# chernov_motherboard.net
KiCad netlist of a schematic drawn in Altium Designer
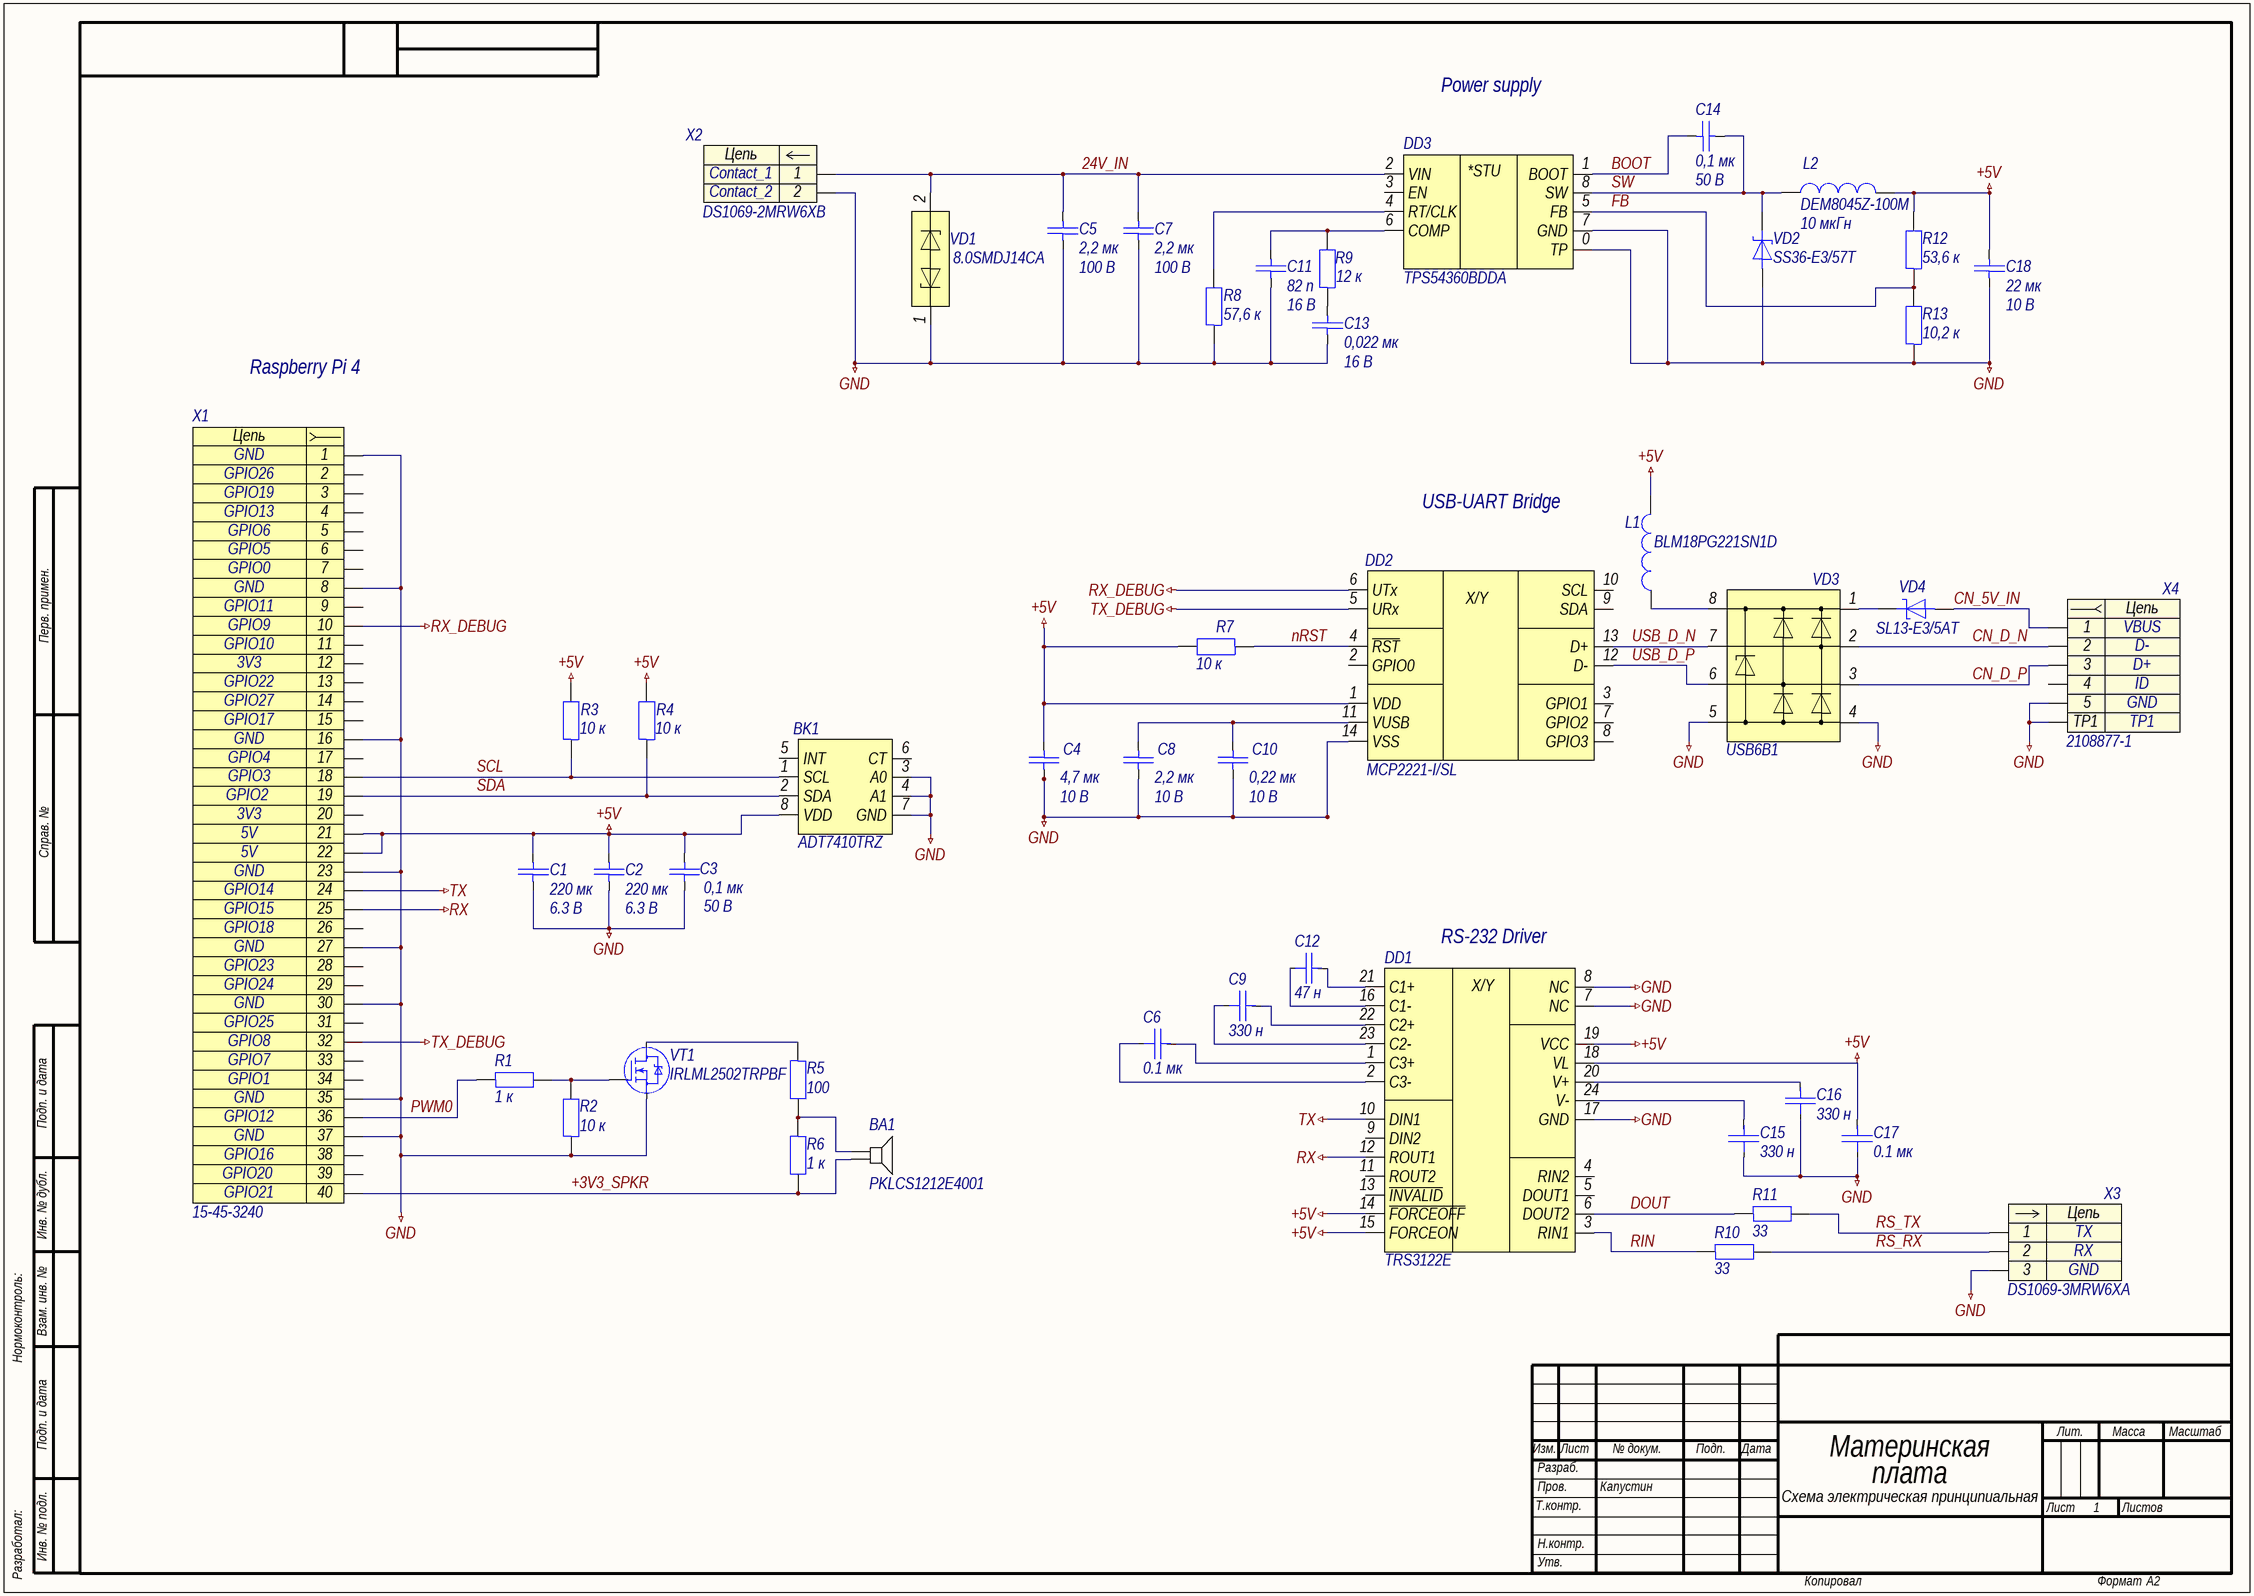
[diagram p0: chernov_motherboard.SchDoc]

(export (version "E")
  (design (tool "Eeschema 10.0.6"))
  (components
    (comp (ref "BA1")
      (value "PKLCS1212E4001")
      (footprint "PKLCS1212E4001")
      (description "Piezoelectric Sounders External Drive SMD Type")
      (libsource (lib "PKLCS1212E4001") (part "PKLCS1212E4001"))
    )
    (comp (ref "BK1")
      (value "ADT7410TRZ")
      (footprint "SOIC-8-P127-490X390X175-L84X41")
      (description "16-бит I2CI цифровой датчик температуры, точность ±0.5°C")
      (libsource (lib "ad22100") (part "TEMP"))
    )
    (comp (ref "C1")
      (value "220 мк")
      (footprint "C1210")
      (description "=Описание")
      (fields (field (name "НАПРЯЖЕНИЕ") "6.3 В"))
      (libsource (lib "Database_Students") (part "CAPACITOR-NONPOLAR"))
    )
    (comp (ref "C2")
      (value "220 мк")
      (footprint "C1210")
      (description "=Описание")
      (fields (field (name "НАПРЯЖЕНИЕ") "6.3 В"))
      (libsource (lib "Database_Students") (part "CAPACITOR-NONPOLAR"))
    )
    (comp (ref "C3")
      (value "0,1 мк")
      (footprint "C0603")
      (description "=Описание")
      (fields (field (name "НАПРЯЖЕНИЕ") "50 В"))
      (libsource (lib "Database_Students") (part "CAPACITOR-NONPOLAR"))
    )
    (comp (ref "C4")
      (value "4,7 мк")
      (footprint "C0603")
      (description "=Описание")
      (fields (field (name "НАПРЯЖЕНИЕ") "10 В"))
      (libsource (lib "Database_Students") (part "C-NONPOLAR"))
    )
    (comp (ref "C5")
      (value "2,2 мк")
      (footprint "C1206")
      (description "=Описание")
      (fields (field (name "НАПРЯЖЕНИЕ") "100 В"))
      (libsource (lib "Database_Students") (part "C-NONPOLAR"))
    )
    (comp (ref "C6")
      (value "0.1 мк")
      (footprint "C0603")
      (description "=Описание")
      (libsource (lib "Database_Students") (part "C-50.0V"))
    )
    (comp (ref "C7")
      (value "2,2 мк")
      (footprint "C1206")
      (description "=Описание")
      (fields (field (name "НАПРЯЖЕНИЕ") "100 В"))
      (libsource (lib "Database_Students") (part "C-NONPOLAR"))
    )
    (comp (ref "C8")
      (value "2,2 мк")
      (footprint "C0603")
      (description "=Описание")
      (fields (field (name "НАПРЯЖЕНИЕ") "10 В"))
      (libsource (lib "Database_Students") (part "C-NONPOLAR"))
    )
    (comp (ref "C9")
      (value "330 н")
      (footprint "C0805")
      (description "=Описание")
      (libsource (lib "Database_Students") (part "C-50.0V"))
    )
    (comp (ref "C10")
      (value "0,22 мк")
      (footprint "C0603")
      (description "=Описание")
      (fields (field (name "НАПРЯЖЕНИЕ") "10 В"))
      (libsource (lib "Database_Students") (part "C-NONPOLAR"))
    )
    (comp (ref "C11")
      (value "82 п")
      (footprint "C0603")
      (description "=Описание")
      (fields (field (name "НАПРЯЖЕНИЕ") "16 В"))
      (libsource (lib "Database_Students") (part "C-NONPOLAR"))
    )
    (comp (ref "C12")
      (value "47 н")
      (footprint "C0603")
      (description "=Описание")
      (libsource (lib "Database_Students") (part "C-50.0V"))
    )
    (comp (ref "C13")
      (value "0,022 мк")
      (footprint "C0603")
      (description "=Описание")
      (fields (field (name "НАПРЯЖЕНИЕ") "16 В"))
      (libsource (lib "Database_Students") (part "C-NONPOLAR"))
    )
    (comp (ref "C14")
      (value "0,1 мк")
      (footprint "C0603")
      (description "=Описание")
      (fields (field (name "НАПРЯЖЕНИЕ") "50 В"))
      (libsource (lib "Database_Students") (part "C-NONPOLAR"))
    )
    (comp (ref "C15")
      (value "330 н")
      (footprint "C0805")
      (description "=Описание")
      (libsource (lib "Database_Students") (part "C-50.0V"))
    )
    (comp (ref "C16")
      (value "330 н")
      (footprint "C0805")
      (description "=Описание")
      (libsource (lib "Database_Students") (part "C-50.0V"))
    )
    (comp (ref "C17")
      (value "0.1 мк")
      (footprint "C0603")
      (description "=Описание")
      (libsource (lib "Database_Students") (part "C-50.0V"))
    )
    (comp (ref "C18")
      (value "22 мк")
      (footprint "C0603")
      (description "=Описание")
      (fields (field (name "НАПРЯЖЕНИЕ") "10 В"))
      (libsource (lib "Database_Students") (part "C-NONPOLAR"))
    )
    (comp (ref "DD1") (value "TRS3122E") (footprint "PQFN_24") (libsource (lib "TRS3122E") (part "TRS3122E")))
    (comp (ref "DD2")
      (value "MCP2221-I/SL")
      (footprint "mcp2221:SOIC127P600X175-14N")
      (libsource (lib "mcp2221") (part "MCP2221-I/SL"))
    )
    (comp (ref "DD3")
      (value "TPS54360BDDA")
      (footprint "HSOIC-8")
      (description "=Описание")
      (libsource (lib "Database_Students") (part "TPS54360BDDA"))
    )
    (comp (ref "L1")
      (value "BLM18PG221SN1D")
      (footprint "BLM-2-0603")
      (description "=Описание")
      (libsource (lib "Database_Students") (part "FERRITE-BEAD"))
    )
    (comp (ref "L2")
      (value "DEM8045Z-100M")
      (footprint "DEM-2-800X800X450")
      (description "=Описание")
      (fields (field (name "ИНДУКТИВНОСТЬ") "10 мкГн"))
      (libsource (lib "Database_Students") (part "INDUCTOR-COMMON"))
    )
    (comp (ref "R1")
      (value "1 к")
      (footprint "R0603")
      (description "=Описание")
      (libsource (lib "Database_Students") (part "RESISTOR-COMMON"))
    )
    (comp (ref "R2")
      (value "10 к")
      (footprint "R0603")
      (description "=Описание")
      (libsource (lib "Database_Students") (part "RESISTOR-COMMON"))
    )
    (comp (ref "R3")
      (value "10 к")
      (footprint "R0603")
      (description "=Описание")
      (libsource (lib "Database_Students") (part "RESISTOR-COMMON"))
    )
    (comp (ref "R4")
      (value "10 к")
      (footprint "R0603")
      (description "=Описание")
      (libsource (lib "Database_Students") (part "RESISTOR-COMMON"))
    )
    (comp (ref "R5")
      (value "100")
      (footprint "R0603")
      (description "=Описание")
      (libsource (lib "Database_Students") (part "RESISTOR-COMMON"))
    )
    (comp (ref "R6")
      (value "1 к")
      (footprint "R0603")
      (description "=Описание")
      (libsource (lib "Database_Students") (part "RESISTOR-COMMON"))
    )
    (comp (ref "R7")
      (value "10 к")
      (footprint "R0603")
      (description "=Описание")
      (libsource (lib "Database_Students") (part "R-COMMON"))
    )
    (comp (ref "R8")
      (value "57,6 к")
      (footprint "R0603")
      (description "=Описание")
      (libsource (lib "Database_Students") (part "RESISTOR-COMMON"))
    )
    (comp (ref "R9")
      (value "12 к")
      (footprint "R0603")
      (description "=Описание")
      (libsource (lib "Database_Students") (part "RESISTOR-COMMON"))
    )
    (comp (ref "R10")
      (value "33")
      (footprint "R0603")
      (description "=Описание")
      (libsource (lib "Database_Students") (part "R-0.05W"))
    )
    (comp (ref "R11")
      (value "33")
      (footprint "R0603")
      (description "=Описание")
      (libsource (lib "Database_Students") (part "R-0.05W"))
    )
    (comp (ref "R12")
      (value "53,6 к")
      (footprint "R0603")
      (description "=Описание")
      (libsource (lib "Database_Students") (part "R-COMMON"))
    )
    (comp (ref "R13")
      (value "10,2 к")
      (footprint "R0603")
      (description "=Описание")
      (libsource (lib "Database_Students") (part "R-COMMON"))
    )
    (comp (ref "VD1")
      (value "8.0SMDJ14CA")
      (footprint "DO-214AB")
      (description "=Описание")
      (libsource (lib "Database_Students") (part "ZENER-BI-DIRECTIONAL"))
    )
    (comp (ref "VD2")
      (value "SS36-E3/57T")
      (footprint "DO-214AB")
      (description "=Описание")
      (libsource (lib "Database_Students") (part "DIODE-SCHOTTKY"))
    )
    (comp (ref "VD3")
      (value "USB6B1")
      (footprint "SO-8")
      (description "=Описание")
      (libsource (lib "Database_Students") (part "USB6B1"))
    )
    (comp (ref "VD4")
      (value "SL13-E3/5AT")
      (footprint "DO-214AC")
      (description "=Описание")
      (libsource (lib "Database_Students") (part "DIODE-SCHOTTKY"))
    )
    (comp (ref "VT1")
      (value "IRLML2502TRPBF")
      (footprint "SOT-23-3-P95-292X237X112")
      (description "=Описание")
      (libsource (lib "Database_Students") (part "MOSFET-N-DIODE-SCHOTTKY"))
    )
    (comp (ref "X1")
      (value "15-45-3240")
      (footprint "15-45-3240")
      (description "=Описание")
      (libsource (lib "Database_Students") (part "HEADER-40-SCT"))
    )
    (comp (ref "X2")
      (value "DS1069-2MRW6XB")
      (footprint "DS1069-2MRW6XB")
      (description "=Описание")
      (libsource (lib "Database_Students") (part "HEADER-2-PLG"))
    )
    (comp (ref "X3")
      (value "DS1069-3MRW6XA")
      (footprint "DS1069-3MRW6XA")
      (description "=Описание")
      (libsource (lib "Database_Students") (part "HEADER-3-PLG"))
    )
    (comp (ref "X4")
      (value "2108877-1")
      (footprint "2108877-1")
      (description "=Описание")
      (libsource (lib "Database_Students") (part "HEADER-5-TP1-SCT"))
    )
  )
  (nets
    (net (code "1") (name "+5V") (class "Default")
      (node (ref "BK1") (pin "8") (pinfunction "VDD_8") (pintype "passive"))
      (node (ref "C1") (pin "1") (pinfunction "1_1") (pintype "passive"))
      (node (ref "C17") (pin "2") (pinfunction "2_2") (pintype "passive"))
      (node (ref "C18") (pin "1") (pinfunction "1_1") (pintype "passive"))
      (node (ref "C2") (pin "1") (pinfunction "1_1") (pintype "passive"))
      (node (ref "C3") (pin "1") (pinfunction "1_1") (pintype "passive"))
      (node (ref "C4") (pin "2") (pinfunction "2_2") (pintype "passive"))
      (node (ref "DD1") (pin "14") (pinfunction "~{FORCEOFF}_14") (pintype "passive"))
      (node (ref "DD1") (pin "15") (pinfunction "FORCEON_15") (pintype "passive"))
      (node (ref "DD1") (pin "18") (pinfunction "VL_18") (pintype "passive"))
      (node (ref "DD1") (pin "19") (pinfunction "VCC_19") (pintype "passive"))
      (node (ref "DD2") (pin "1") (pinfunction "VDD_1") (pintype "passive"))
      (node (ref "L1") (pin "1") (pinfunction "1_1") (pintype "passive"))
      (node (ref "L2") (pin "2") (pinfunction "2_2") (pintype "passive"))
      (node (ref "R12") (pin "2") (pinfunction "2_2") (pintype "passive"))
      (node (ref "R3") (pin "2") (pinfunction "2_2") (pintype "passive"))
      (node (ref "R4") (pin "2") (pinfunction "2_2") (pintype "passive"))
      (node (ref "R7") (pin "2") (pinfunction "2_2") (pintype "passive"))
      (node (ref "X1") (pin "21") (pinfunction "21_21") (pintype "passive"))
      (node (ref "X1") (pin "22") (pinfunction "22_22") (pintype "passive"))
    )
    (net (code "2") (name "/+3V3_SPKR") (class "Default")
      (node (ref "BA1") (pin "2") (pinfunction "2_2") (pintype "passive"))
      (node (ref "R6") (pin "2") (pinfunction "2_2") (pintype "passive"))
      (node (ref "X1") (pin "40") (pinfunction "40_40") (pintype "passive"))
    )
    (net (code "3") (name "/24V_IN") (class "Default")
      (node (ref "C5") (pin "1") (pinfunction "1_1") (pintype "passive"))
      (node (ref "C7") (pin "1") (pinfunction "1_1") (pintype "passive"))
      (node (ref "DD3") (pin "2") (pinfunction "VIN_2") (pintype "passive"))
      (node (ref "VD1") (pin "2") (pinfunction "2_2") (pintype "passive"))
      (node (ref "X2") (pin "1") (pinfunction "1_1") (pintype "passive"))
    )
    (net (code "4") (name "/BOOT") (class "Default")
      (node (ref "C14") (pin "2") (pinfunction "2_2") (pintype "passive"))
      (node (ref "DD3") (pin "1") (pinfunction "BOOT_1") (pintype "passive"))
    )
    (net (code "5") (name "/CN_5V_IN") (class "Default")
      (node (ref "VD4") (pin "2") (pinfunction "2_2") (pintype "passive"))
      (node (ref "X4") (pin "1") (pinfunction "1_1") (pintype "passive"))
    )
    (net (code "6") (name "/CN_D_N") (class "Default")
      (node (ref "VD3") (pin "2") (pinfunction "2_2") (pintype "passive"))
      (node (ref "X4") (pin "2") (pinfunction "2_2") (pintype "passive"))
    )
    (net (code "7") (name "/CN_D_P") (class "Default")
      (node (ref "VD3") (pin "3") (pinfunction "3_3") (pintype "passive"))
      (node (ref "X4") (pin "3") (pinfunction "3_3") (pintype "passive"))
    )
    (net (code "8") (name "/DOUT") (class "Default")
      (node (ref "DD1") (pin "6") (pinfunction "DOUT2_6") (pintype "passive"))
      (node (ref "R11") (pin "1") (pinfunction "1_1") (pintype "passive"))
    )
    (net (code "9") (name "/FB") (class "Default")
      (node (ref "DD3") (pin "5") (pinfunction "FB_5") (pintype "passive"))
      (node (ref "R12") (pin "1") (pinfunction "1_1") (pintype "passive"))
      (node (ref "R13") (pin "2") (pinfunction "2_2") (pintype "passive"))
    )
    (net (code "10") (name "/PWM0") (class "Default")
      (node (ref "R1") (pin "1") (pinfunction "1_1") (pintype "passive"))
      (node (ref "X1") (pin "36") (pinfunction "36_36") (pintype "passive"))
    )
    (net (code "11") (name "/RIN") (class "Default")
      (node (ref "DD1") (pin "3") (pinfunction "RIN1_3") (pintype "passive"))
      (node (ref "R10") (pin "1") (pinfunction "1_1") (pintype "passive"))
    )
    (net (code "12") (name "/RS_RX") (class "Default")
      (node (ref "R10") (pin "2") (pinfunction "2_2") (pintype "passive"))
      (node (ref "X3") (pin "2") (pinfunction "2_2") (pintype "passive"))
    )
    (net (code "13") (name "/RS_TX") (class "Default")
      (node (ref "R11") (pin "2") (pinfunction "2_2") (pintype "passive"))
      (node (ref "X3") (pin "1") (pinfunction "1_1") (pintype "passive"))
    )
    (net (code "14") (name "/SCL") (class "Default")
      (node (ref "BK1") (pin "1") (pinfunction "SCL_1") (pintype "passive"))
      (node (ref "R3") (pin "1") (pinfunction "1_1") (pintype "passive"))
      (node (ref "X1") (pin "18") (pinfunction "18_18") (pintype "passive"))
    )
    (net (code "15") (name "/SDA") (class "Default")
      (node (ref "BK1") (pin "2") (pinfunction "SDA_2") (pintype "passive"))
      (node (ref "R4") (pin "1") (pinfunction "1_1") (pintype "passive"))
      (node (ref "X1") (pin "19") (pinfunction "19_19") (pintype "passive"))
    )
    (net (code "16") (name "/SW") (class "Default")
      (node (ref "C14") (pin "1") (pinfunction "1_1") (pintype "passive"))
      (node (ref "DD3") (pin "8") (pinfunction "SW_8") (pintype "passive"))
      (node (ref "L2") (pin "1") (pinfunction "1_1") (pintype "passive"))
      (node (ref "VD2") (pin "1") (pinfunction "1_1") (pintype "passive"))
    )
    (net (code "17") (name "/USB_D_N") (class "Default")
      (node (ref "DD2") (pin "13") (pinfunction "D+_13") (pintype "passive"))
      (node (ref "VD3") (pin "7") (pinfunction "7_7") (pintype "passive"))
    )
    (net (code "18") (name "/USB_D_P") (class "Default")
      (node (ref "DD2") (pin "12") (pinfunction "D-_12") (pintype "passive"))
      (node (ref "VD3") (pin "6") (pinfunction "6_6") (pintype "passive"))
    )
    (net (code "19") (name "/nRST") (class "Default")
      (node (ref "DD2") (pin "4") (pinfunction "~{RST}_4") (pintype "passive"))
      (node (ref "R7") (pin "1") (pinfunction "1_1") (pintype "passive"))
    )
    (net (code "20") (name "GND") (class "Default")
      (node (ref "BK1") (pin "3") (pinfunction "A0_3") (pintype "passive"))
      (node (ref "BK1") (pin "4") (pinfunction "A1_4") (pintype "passive"))
      (node (ref "BK1") (pin "7") (pinfunction "GND_7") (pintype "passive"))
      (node (ref "C1") (pin "2") (pinfunction "2_2") (pintype "passive"))
      (node (ref "C10") (pin "1") (pinfunction "1_1") (pintype "passive"))
      (node (ref "C11") (pin "2") (pinfunction "2_2") (pintype "passive"))
      (node (ref "C13") (pin "2") (pinfunction "2_2") (pintype "passive"))
      (node (ref "C15") (pin "1") (pinfunction "1_1") (pintype "passive"))
      (node (ref "C16") (pin "1") (pinfunction "1_1") (pintype "passive"))
      (node (ref "C17") (pin "1") (pinfunction "1_1") (pintype "passive"))
      (node (ref "C18") (pin "2") (pinfunction "2_2") (pintype "passive"))
      (node (ref "C2") (pin "2") (pinfunction "2_2") (pintype "passive"))
      (node (ref "C3") (pin "2") (pinfunction "2_2") (pintype "passive"))
      (node (ref "C4") (pin "1") (pinfunction "1_1") (pintype "passive"))
      (node (ref "C5") (pin "2") (pinfunction "2_2") (pintype "passive"))
      (node (ref "C7") (pin "2") (pinfunction "2_2") (pintype "passive"))
      (node (ref "C8") (pin "1") (pinfunction "1_1") (pintype "passive"))
      (node (ref "DD1") (pin "17") (pinfunction "GND_17") (pintype "passive"))
      (node (ref "DD1") (pin "7") (pinfunction "NC_7") (pintype "passive"))
      (node (ref "DD1") (pin "8") (pinfunction "NC_8") (pintype "passive"))
      (node (ref "DD2") (pin "14") (pinfunction "VSS_14") (pintype "passive"))
      (node (ref "DD3") (pin "0") (pinfunction "TP_0") (pintype "passive"))
      (node (ref "DD3") (pin "7") (pinfunction "GND_7") (pintype "passive"))
      (node (ref "R13") (pin "1") (pinfunction "1_1") (pintype "passive"))
      (node (ref "R2") (pin "1") (pinfunction "1_1") (pintype "passive"))
      (node (ref "R8") (pin "1") (pinfunction "1_1") (pintype "passive"))
      (node (ref "VD1") (pin "1") (pinfunction "1_1") (pintype "passive"))
      (node (ref "VD2") (pin "2") (pinfunction "2_2") (pintype "passive"))
      (node (ref "VD3") (pin "4") (pinfunction "4_4") (pintype "passive"))
      (node (ref "VD3") (pin "5") (pinfunction "5_5") (pintype "passive"))
      (node (ref "VT1") (pin "S") (pinfunction "S_S") (pintype "passive"))
      (node (ref "X1") (pin "1") (pinfunction "1_1") (pintype "passive"))
      (node (ref "X1") (pin "16") (pinfunction "16_16") (pintype "passive"))
      (node (ref "X1") (pin "23") (pinfunction "23_23") (pintype "passive"))
      (node (ref "X1") (pin "27") (pinfunction "27_27") (pintype "passive"))
      (node (ref "X1") (pin "30") (pinfunction "30_30") (pintype "passive"))
      (node (ref "X1") (pin "35") (pinfunction "35_35") (pintype "passive"))
      (node (ref "X1") (pin "37") (pinfunction "37_37") (pintype "passive"))
      (node (ref "X1") (pin "8") (pinfunction "8_8") (pintype "passive"))
      (node (ref "X2") (pin "2") (pinfunction "2_2") (pintype "passive"))
      (node (ref "X3") (pin "3") (pinfunction "3_3") (pintype "passive"))
      (node (ref "X4") (pin "5") (pinfunction "5_5") (pintype "passive"))
      (node (ref "X4") (pin "TP1") (pinfunction "TP1_TP1") (pintype "passive"))
    )
    (net (code "21") (name "Net-(BA1-Pad1)") (class "Default")
      (node (ref "BA1") (pin "1") (pinfunction "1_1") (pintype "passive"))
      (node (ref "R5") (pin "2") (pinfunction "2_2") (pintype "passive"))
      (node (ref "R6") (pin "1") (pinfunction "1_1") (pintype "passive"))
    )
    (net (code "22") (name "Net-(C13-Pad1)") (class "Default")
      (node (ref "C13") (pin "1") (pinfunction "1_1") (pintype "passive"))
      (node (ref "R9") (pin "1") (pinfunction "1_1") (pintype "passive"))
    )
    (net (code "23") (name "Net-(DD1-C1+)") (class "Default")
      (node (ref "C12") (pin "2") (pinfunction "2_2") (pintype "passive"))
      (node (ref "DD1") (pin "21") (pinfunction "C1+_21") (pintype "passive"))
    )
    (net (code "24") (name "Net-(DD1-C1-)") (class "Default")
      (node (ref "C12") (pin "1") (pinfunction "1_1") (pintype "passive"))
      (node (ref "DD1") (pin "16") (pinfunction "C1-_16") (pintype "passive"))
    )
    (net (code "25") (name "Net-(DD1-C2+)") (class "Default")
      (node (ref "C9") (pin "2") (pinfunction "2_2") (pintype "passive"))
      (node (ref "DD1") (pin "22") (pinfunction "C2+_22") (pintype "passive"))
    )
    (net (code "26") (name "Net-(DD1-C2-)") (class "Default")
      (node (ref "C9") (pin "1") (pinfunction "1_1") (pintype "passive"))
      (node (ref "DD1") (pin "23") (pinfunction "C2-_23") (pintype "passive"))
    )
    (net (code "27") (name "Net-(DD1-C3+)") (class "Default")
      (node (ref "C6") (pin "2") (pinfunction "2_2") (pintype "passive"))
      (node (ref "DD1") (pin "1") (pinfunction "C3+_1") (pintype "passive"))
    )
    (net (code "28") (name "Net-(DD1-C3-)") (class "Default")
      (node (ref "C6") (pin "1") (pinfunction "1_1") (pintype "passive"))
      (node (ref "DD1") (pin "2") (pinfunction "C3-_2") (pintype "passive"))
    )
    (net (code "29") (name "Net-(DD1-V+)") (class "Default")
      (node (ref "C16") (pin "2") (pinfunction "2_2") (pintype "passive"))
      (node (ref "DD1") (pin "20") (pinfunction "V+_20") (pintype "passive"))
    )
    (net (code "30") (name "Net-(DD1-V-)") (class "Default")
      (node (ref "C15") (pin "2") (pinfunction "2_2") (pintype "passive"))
      (node (ref "DD1") (pin "24") (pinfunction "V-_24") (pintype "passive"))
    )
    (net (code "31") (name "Net-(DD2-VUSB)") (class "Default")
      (node (ref "C10") (pin "2") (pinfunction "2_2") (pintype "passive"))
      (node (ref "C8") (pin "2") (pinfunction "2_2") (pintype "passive"))
      (node (ref "DD2") (pin "11") (pinfunction "VUSB_11") (pintype "passive"))
    )
    (net (code "32") (name "Net-(DD3-COMP)") (class "Default")
      (node (ref "C11") (pin "1") (pinfunction "1_1") (pintype "passive"))
      (node (ref "DD3") (pin "6") (pinfunction "COMP_6") (pintype "passive"))
      (node (ref "R9") (pin "2") (pinfunction "2_2") (pintype "passive"))
    )
    (net (code "33") (name "Net-(DD3-RT{slash}CLK)") (class "Default")
      (node (ref "DD3") (pin "4") (pinfunction "RT/CLK_4") (pintype "passive"))
      (node (ref "R8") (pin "2") (pinfunction "2_2") (pintype "passive"))
    )
    (net (code "34") (name "Net-(L1-Pad2)") (class "Default")
      (node (ref "L1") (pin "2") (pinfunction "2_2") (pintype "passive"))
      (node (ref "VD3") (pin "8") (pinfunction "8_8") (pintype "passive"))
    )
    (net (code "35") (name "Net-(R1-Pad2)") (class "Default")
      (node (ref "R1") (pin "2") (pinfunction "2_2") (pintype "passive"))
      (node (ref "R2") (pin "2") (pinfunction "2_2") (pintype "passive"))
      (node (ref "VT1") (pin "G") (pinfunction "G_G") (pintype "passive"))
    )
    (net (code "36") (name "Net-(R5-Pad1)") (class "Default")
      (node (ref "R5") (pin "1") (pinfunction "1_1") (pintype "passive"))
      (node (ref "VT1") (pin "D") (pinfunction "D_D") (pintype "passive"))
    )
    (net (code "37") (name "Net-(VD3-Pad1)") (class "Default")
      (node (ref "VD3") (pin "1") (pinfunction "1_1") (pintype "passive"))
      (node (ref "VD4") (pin "1") (pinfunction "1_1") (pintype "passive"))
    )
    (net (code "38") (name "RX") (class "Default")
      (node (ref "DD1") (pin "12") (pinfunction "ROUT1_12") (pintype "passive"))
      (node (ref "X1") (pin "25") (pinfunction "25_25") (pintype "passive"))
    )
    (net (code "39") (name "RX_DEBUG") (class "Default")
      (node (ref "DD2") (pin "6") (pinfunction "UTx_6") (pintype "passive"))
      (node (ref "X1") (pin "10") (pinfunction "10_10") (pintype "passive"))
    )
    (net (code "40") (name "TX") (class "Default")
      (node (ref "DD1") (pin "10") (pinfunction "DIN1_10") (pintype "passive"))
      (node (ref "X1") (pin "24") (pinfunction "24_24") (pintype "passive"))
    )
    (net (code "41") (name "TX_DEBUG") (class "Default")
      (node (ref "DD2") (pin "5") (pinfunction "URx_5") (pintype "passive"))
      (node (ref "X1") (pin "32") (pinfunction "32_32") (pintype "passive"))
    )
    (net (code "42") (name "unconnected-(BK1-CT-Pad6)") (class "Default")
      (node (ref "BK1") (pin "6") (pinfunction "CT_6") (pintype "passive"))
    )
    (net (code "43") (name "unconnected-(BK1-INT-Pad5)") (class "Default")
      (node (ref "BK1") (pin "5") (pinfunction "INT_5") (pintype "passive"))
    )
    (net (code "44") (name "unconnected-(DD1-DIN2-Pad9)") (class "Default")
      (node (ref "DD1") (pin "9") (pinfunction "DIN2_9") (pintype "passive"))
    )
    (net (code "45") (name "unconnected-(DD1-DOUT1-Pad5)") (class "Default")
      (node (ref "DD1") (pin "5") (pinfunction "DOUT1_5") (pintype "passive"))
    )
    (net (code "46") (name "unconnected-(DD1-RIN2-Pad4)") (class "Default")
      (node (ref "DD1") (pin "4") (pinfunction "RIN2_4") (pintype "passive"))
    )
    (net (code "47") (name "unconnected-(DD1-ROUT2-Pad11)") (class "Default")
      (node (ref "DD1") (pin "11") (pinfunction "ROUT2_11") (pintype "passive"))
    )
    (net (code "48") (name "unconnected-(DD1-~{INVALID}-Pad13)") (class "Default")
      (node (ref "DD1") (pin "13") (pinfunction "~{INVALID}_13") (pintype "passive"))
    )
    (net (code "49") (name "unconnected-(DD2-GPIO0-Pad2)") (class "Default")
      (node (ref "DD2") (pin "2") (pinfunction "GPIO0_2") (pintype "passive"))
    )
    (net (code "50") (name "unconnected-(DD2-GPIO1-Pad3)") (class "Default")
      (node (ref "DD2") (pin "3") (pinfunction "GPIO1_3") (pintype "passive"))
    )
    (net (code "51") (name "unconnected-(DD2-GPIO2-Pad7)") (class "Default")
      (node (ref "DD2") (pin "7") (pinfunction "GPIO2_7") (pintype "passive"))
    )
    (net (code "52") (name "unconnected-(DD2-GPIO3-Pad8)") (class "Default")
      (node (ref "DD2") (pin "8") (pinfunction "GPIO3_8") (pintype "passive"))
    )
    (net (code "53") (name "unconnected-(DD2-SCL-Pad10)") (class "Default")
      (node (ref "DD2") (pin "10") (pinfunction "SCL_10") (pintype "passive"))
    )
    (net (code "54") (name "unconnected-(DD2-SDA-Pad9)") (class "Default")
      (node (ref "DD2") (pin "9") (pinfunction "SDA_9") (pintype "passive"))
    )
    (net (code "55") (name "unconnected-(DD3-EN-Pad3)") (class "Default")
      (node (ref "DD3") (pin "3") (pinfunction "EN_3") (pintype "passive"))
    )
    (net (code "56") (name "unconnected-(X1-Pad2)") (class "Default")
      (node (ref "X1") (pin "2") (pinfunction "2_2") (pintype "passive"))
    )
    (net (code "57") (name "unconnected-(X1-Pad3)") (class "Default")
      (node (ref "X1") (pin "3") (pinfunction "3_3") (pintype "passive"))
    )
    (net (code "58") (name "unconnected-(X1-Pad4)") (class "Default")
      (node (ref "X1") (pin "4") (pinfunction "4_4") (pintype "passive"))
    )
    (net (code "59") (name "unconnected-(X1-Pad5)") (class "Default")
      (node (ref "X1") (pin "5") (pinfunction "5_5") (pintype "passive"))
    )
    (net (code "60") (name "unconnected-(X1-Pad6)") (class "Default")
      (node (ref "X1") (pin "6") (pinfunction "6_6") (pintype "passive"))
    )
    (net (code "61") (name "unconnected-(X1-Pad7)") (class "Default")
      (node (ref "X1") (pin "7") (pinfunction "7_7") (pintype "passive"))
    )
    (net (code "62") (name "unconnected-(X1-Pad9)") (class "Default")
      (node (ref "X1") (pin "9") (pinfunction "9_9") (pintype "passive"))
    )
    (net (code "63") (name "unconnected-(X1-Pad11)") (class "Default")
      (node (ref "X1") (pin "11") (pinfunction "11_11") (pintype "passive"))
    )
    (net (code "64") (name "unconnected-(X1-Pad12)") (class "Default")
      (node (ref "X1") (pin "12") (pinfunction "12_12") (pintype "passive"))
    )
    (net (code "65") (name "unconnected-(X1-Pad13)") (class "Default")
      (node (ref "X1") (pin "13") (pinfunction "13_13") (pintype "passive"))
    )
    (net (code "66") (name "unconnected-(X1-Pad14)") (class "Default")
      (node (ref "X1") (pin "14") (pinfunction "14_14") (pintype "passive"))
    )
    (net (code "67") (name "unconnected-(X1-Pad15)") (class "Default")
      (node (ref "X1") (pin "15") (pinfunction "15_15") (pintype "passive"))
    )
    (net (code "68") (name "unconnected-(X1-Pad17)") (class "Default")
      (node (ref "X1") (pin "17") (pinfunction "17_17") (pintype "passive"))
    )
    (net (code "69") (name "unconnected-(X1-Pad20)") (class "Default")
      (node (ref "X1") (pin "20") (pinfunction "20_20") (pintype "passive"))
    )
    (net (code "70") (name "unconnected-(X1-Pad26)") (class "Default")
      (node (ref "X1") (pin "26") (pinfunction "26_26") (pintype "passive"))
    )
    (net (code "71") (name "unconnected-(X1-Pad28)") (class "Default")
      (node (ref "X1") (pin "28") (pinfunction "28_28") (pintype "passive"))
    )
    (net (code "72") (name "unconnected-(X1-Pad29)") (class "Default")
      (node (ref "X1") (pin "29") (pinfunction "29_29") (pintype "passive"))
    )
    (net (code "73") (name "unconnected-(X1-Pad32)") (class "Default")
      (node (ref "X1") (pin "32") (pinfunction "32_32") (pintype "passive"))
    )
    (net (code "74") (name "unconnected-(X1-Pad33)") (class "Default")
      (node (ref "X1") (pin "33") (pinfunction "33_33") (pintype "passive"))
    )
    (net (code "75") (name "unconnected-(X1-Pad34)") (class "Default")
      (node (ref "X1") (pin "34") (pinfunction "34_34") (pintype "passive"))
    )
    (net (code "76") (name "unconnected-(X1-Pad38)") (class "Default")
      (node (ref "X1") (pin "38") (pinfunction "38_38") (pintype "passive"))
    )
    (net (code "77") (name "unconnected-(X1-Pad39)") (class "Default")
      (node (ref "X1") (pin "39") (pinfunction "39_39") (pintype "passive"))
    )
    (net (code "78") (name "unconnected-(X4-Pad4)") (class "Default")
      (node (ref "X4") (pin "4") (pinfunction "4_4") (pintype "passive"))
    )
  )
)
